# Wheatstone_bridge.net
KiCad netlist of a schematic drawn in EAGLE
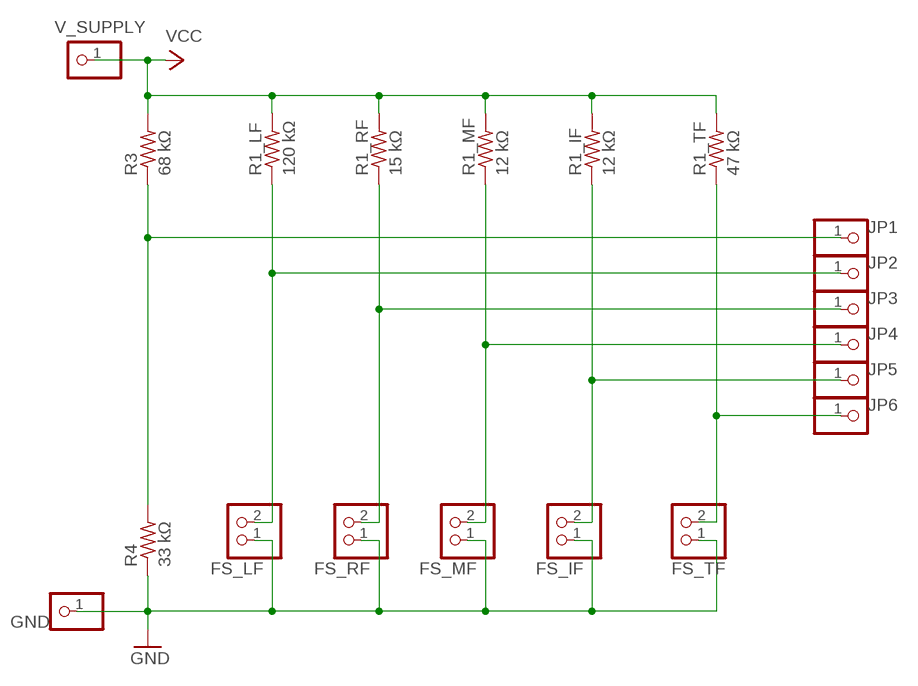
[diagram p0: schematic, sheet 1]

(export (version "E")
  (design (tool "Eeschema 10.0.6"))
  (components
    (comp (ref "FS_IF")
      (value "PINHD-1X2")
      (footprint "eagle-import:1X02")
      (libsource (lib "eagle-import") (part "PINHD-1X2"))
    )
    (comp (ref "FS_LF")
      (value "PINHD-1X2")
      (footprint "eagle-import:1X02")
      (libsource (lib "eagle-import") (part "PINHD-1X2"))
    )
    (comp (ref "FS_MF")
      (value "PINHD-1X2")
      (footprint "eagle-import:1X02")
      (libsource (lib "eagle-import") (part "PINHD-1X2"))
    )
    (comp (ref "FS_RF")
      (value "PINHD-1X2")
      (footprint "eagle-import:1X02")
      (libsource (lib "eagle-import") (part "PINHD-1X2"))
    )
    (comp (ref "FS_TF")
      (value "PINHD-1X2")
      (footprint "eagle-import:1X02")
      (libsource (lib "eagle-import") (part "PINHD-1X2"))
    )
    (comp (ref "GND")
      (value "PINHD-1X1")
      (footprint "eagle-import:1X01")
      (libsource (lib "eagle-import") (part "PINHD-1X1"))
    )
    (comp (ref "JP1")
      (value "PINHD-1X1")
      (footprint "eagle-import:1X01")
      (libsource (lib "eagle-import") (part "PINHD-1X1"))
    )
    (comp (ref "JP2")
      (value "PINHD-1X1")
      (footprint "eagle-import:1X01")
      (libsource (lib "eagle-import") (part "PINHD-1X1"))
    )
    (comp (ref "JP3")
      (value "PINHD-1X1")
      (footprint "eagle-import:1X01")
      (libsource (lib "eagle-import") (part "PINHD-1X1"))
    )
    (comp (ref "JP4")
      (value "PINHD-1X1")
      (footprint "eagle-import:1X01")
      (libsource (lib "eagle-import") (part "PINHD-1X1"))
    )
    (comp (ref "JP5")
      (value "PINHD-1X1")
      (footprint "eagle-import:1X01")
      (libsource (lib "eagle-import") (part "PINHD-1X1"))
    )
    (comp (ref "JP6")
      (value "PINHD-1X1")
      (footprint "eagle-import:1X01")
      (libsource (lib "eagle-import") (part "PINHD-1X1"))
    )
    (comp (ref "R1_IF")
      (value "12 kΩ")
      (footprint "eagle-import:0207_7")
      (libsource (lib "eagle-import") (part "R-US_0207/7"))
    )
    (comp (ref "R1_LF")
      (value "120 kΩ")
      (footprint "eagle-import:0207_7")
      (libsource (lib "eagle-import") (part "R-US_0207/7"))
    )
    (comp (ref "R1_MF")
      (value "12 kΩ")
      (footprint "eagle-import:0207_7")
      (libsource (lib "eagle-import") (part "R-US_0207/7"))
    )
    (comp (ref "R1_RF")
      (value "15 kΩ")
      (footprint "eagle-import:0207_7")
      (libsource (lib "eagle-import") (part "R-US_0207/7"))
    )
    (comp (ref "R1_TF")
      (value "47 kΩ")
      (footprint "eagle-import:0207_7")
      (libsource (lib "eagle-import") (part "R-US_0207/7"))
    )
    (comp (ref "R3")
      (value "68 kΩ")
      (footprint "eagle-import:0207_7")
      (libsource (lib "eagle-import") (part "R-US_0207/7"))
    )
    (comp (ref "R4")
      (value "33 kΩ")
      (footprint "eagle-import:0207_7")
      (libsource (lib "eagle-import") (part "R-US_0207/7"))
    )
    (comp (ref "V_SUPPLY")
      (value "PINHD-1X1")
      (footprint "eagle-import:1X01")
      (libsource (lib "eagle-import") (part "PINHD-1X1"))
    )
  )
  (nets
    (net (code "1") (name "GND") (class "Default")
      (node (ref "FS_IF") (pin "1") (pinfunction "1_1") (pintype "passive"))
      (node (ref "FS_LF") (pin "1") (pinfunction "1_1") (pintype "passive"))
      (node (ref "FS_MF") (pin "1") (pinfunction "1_1") (pintype "passive"))
      (node (ref "FS_RF") (pin "1") (pinfunction "1_1") (pintype "passive"))
      (node (ref "FS_TF") (pin "1") (pinfunction "1_1") (pintype "passive"))
      (node (ref "GND") (pin "1") (pinfunction "1_1") (pintype "passive"))
      (node (ref "R4") (pin "1") (pinfunction "1_1") (pintype "passive"))
    )
    (net (code "2") (name "Net-(FS_IF-Pad2)") (class "Default")
      (node (ref "FS_IF") (pin "2") (pinfunction "2_2") (pintype "passive"))
      (node (ref "JP5") (pin "1") (pinfunction "1_1") (pintype "passive"))
      (node (ref "R1_IF") (pin "1") (pinfunction "1_1") (pintype "passive"))
    )
    (net (code "3") (name "Net-(FS_LF-Pad2)") (class "Default")
      (node (ref "FS_LF") (pin "2") (pinfunction "2_2") (pintype "passive"))
      (node (ref "JP2") (pin "1") (pinfunction "1_1") (pintype "passive"))
      (node (ref "R1_LF") (pin "1") (pinfunction "1_1") (pintype "passive"))
    )
    (net (code "4") (name "Net-(FS_MF-Pad2)") (class "Default")
      (node (ref "FS_MF") (pin "2") (pinfunction "2_2") (pintype "passive"))
      (node (ref "JP4") (pin "1") (pinfunction "1_1") (pintype "passive"))
      (node (ref "R1_MF") (pin "1") (pinfunction "1_1") (pintype "passive"))
    )
    (net (code "5") (name "Net-(FS_RF-Pad2)") (class "Default")
      (node (ref "FS_RF") (pin "2") (pinfunction "2_2") (pintype "passive"))
      (node (ref "JP3") (pin "1") (pinfunction "1_1") (pintype "passive"))
      (node (ref "R1_RF") (pin "1") (pinfunction "1_1") (pintype "passive"))
    )
    (net (code "6") (name "Net-(FS_TF-Pad2)") (class "Default")
      (node (ref "FS_TF") (pin "2") (pinfunction "2_2") (pintype "passive"))
      (node (ref "JP6") (pin "1") (pinfunction "1_1") (pintype "passive"))
      (node (ref "R1_TF") (pin "1") (pinfunction "1_1") (pintype "passive"))
    )
    (net (code "7") (name "Net-(JP1-Pad1)") (class "Default")
      (node (ref "JP1") (pin "1") (pinfunction "1_1") (pintype "passive"))
      (node (ref "R3") (pin "1") (pinfunction "1_1") (pintype "passive"))
      (node (ref "R4") (pin "2") (pinfunction "2_2") (pintype "passive"))
    )
    (net (code "8") (name "VCC") (class "Default")
      (node (ref "R1_IF") (pin "2") (pinfunction "2_2") (pintype "passive"))
      (node (ref "R1_LF") (pin "2") (pinfunction "2_2") (pintype "passive"))
      (node (ref "R1_MF") (pin "2") (pinfunction "2_2") (pintype "passive"))
      (node (ref "R1_RF") (pin "2") (pinfunction "2_2") (pintype "passive"))
      (node (ref "R1_TF") (pin "2") (pinfunction "2_2") (pintype "passive"))
      (node (ref "R3") (pin "2") (pinfunction "2_2") (pintype "passive"))
      (node (ref "V_SUPPLY") (pin "1") (pinfunction "1_1") (pintype "passive"))
    )
  )
)
